# MainBoard_MCU_RF.net
KiCad netlist of a schematic drawn in Altium Designer
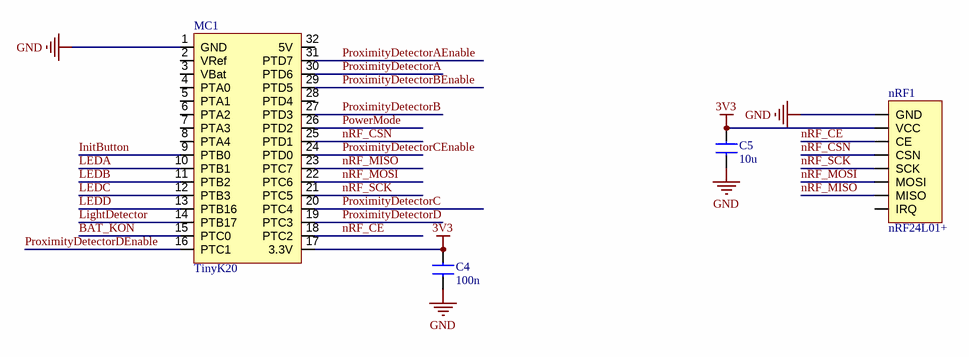
[diagram p0: MainBoard_MCU_RF.SchDoc]

(export (version "E")
  (design (tool "Eeschema 10.0.6"))
  (components
    (comp (ref "C4")
      (value "100n")
      (footprint "0805_C")
      (description "Normaler Kondensator")
      (libsource (lib "MainBoard") (part "C?"))
    )
    (comp (ref "C5")
      (value "10u")
      (footprint "0805_C")
      (description "Normaler Kondensator")
      (libsource (lib "MainBoard") (part "C?"))
    )
    (comp (ref "MC1") (value "TinyK20") (footprint "DIP32") (libsource (lib "MainBoard") (part "TinyK20")))
    (comp (ref "nRF1")
      (value "nRF24L01+")
      (footprint "CON_THT_2x4P_RM2.54_Stiftl")
      (libsource (lib "MainBoard") (part "Bluefruit"))
    )
  )
  (nets
    (net (code "1") (name "/BAT_KON") (class "Default")
      (node (ref "MC1") (pin "15") (pinfunction "PTC0_15") (pintype "passive"))
    )
    (net (code "2") (name "/InitButton") (class "Default")
      (node (ref "MC1") (pin "9") (pinfunction "PTB0_9") (pintype "passive"))
    )
    (net (code "3") (name "/LEDA") (class "Default")
      (node (ref "MC1") (pin "10") (pinfunction "PTB1_10") (pintype "passive"))
    )
    (net (code "4") (name "/LEDB") (class "Default")
      (node (ref "MC1") (pin "11") (pinfunction "PTB2_11") (pintype "passive"))
    )
    (net (code "5") (name "/LEDC") (class "Default")
      (node (ref "MC1") (pin "12") (pinfunction "PTB3_12") (pintype "passive"))
    )
    (net (code "6") (name "/LEDD") (class "Default")
      (node (ref "MC1") (pin "13") (pinfunction "PTB16_13") (pintype "passive"))
    )
    (net (code "7") (name "/LightDetector") (class "Default")
      (node (ref "MC1") (pin "14") (pinfunction "PTB17_14") (pintype "passive"))
    )
    (net (code "8") (name "/PowerMode") (class "Default")
      (node (ref "MC1") (pin "26") (pinfunction "PTD2_26") (pintype "passive"))
    )
    (net (code "9") (name "/ProximityDetectorA") (class "Default")
      (node (ref "MC1") (pin "30") (pinfunction "PTD6_30") (pintype "passive"))
    )
    (net (code "10") (name "/ProximityDetectorAEnable") (class "Default")
      (node (ref "MC1") (pin "31") (pinfunction "PTD7_31") (pintype "passive"))
    )
    (net (code "11") (name "/ProximityDetectorB") (class "Default")
      (node (ref "MC1") (pin "27") (pinfunction "PTD3_27") (pintype "passive"))
    )
    (net (code "12") (name "/ProximityDetectorBEnable") (class "Default")
      (node (ref "MC1") (pin "29") (pinfunction "PTD5_29") (pintype "passive"))
    )
    (net (code "13") (name "/ProximityDetectorC") (class "Default")
      (node (ref "MC1") (pin "20") (pinfunction "PTC4_20") (pintype "passive"))
    )
    (net (code "14") (name "/ProximityDetectorCEnable") (class "Default")
      (node (ref "MC1") (pin "24") (pinfunction "PTD0_24") (pintype "passive"))
    )
    (net (code "15") (name "/ProximityDetectorD") (class "Default")
      (node (ref "MC1") (pin "19") (pinfunction "PTC3_19") (pintype "passive"))
    )
    (net (code "16") (name "/ProximityDetectorDEnable") (class "Default")
      (node (ref "MC1") (pin "16") (pinfunction "PTC1_16") (pintype "passive"))
    )
    (net (code "17") (name "/nRF_CE") (class "Default")
      (node (ref "MC1") (pin "18") (pinfunction "PTC2_18") (pintype "passive"))
      (node (ref "nRF1") (pin "3") (pinfunction "CE_3") (pintype "passive"))
    )
    (net (code "18") (name "/nRF_CSN") (class "Default")
      (node (ref "MC1") (pin "25") (pinfunction "PTD1_25") (pintype "passive"))
      (node (ref "nRF1") (pin "4") (pinfunction "CSN_4") (pintype "passive"))
    )
    (net (code "19") (name "/nRF_MISO") (class "Default")
      (node (ref "MC1") (pin "23") (pinfunction "PTC7_23") (pintype "passive"))
      (node (ref "nRF1") (pin "7") (pinfunction "MISO_7") (pintype "passive"))
    )
    (net (code "20") (name "/nRF_MOSI") (class "Default")
      (node (ref "MC1") (pin "22") (pinfunction "PTC6_22") (pintype "passive"))
      (node (ref "nRF1") (pin "6") (pinfunction "MOSI_6") (pintype "passive"))
    )
    (net (code "21") (name "/nRF_SCK") (class "Default")
      (node (ref "MC1") (pin "21") (pinfunction "PTC5_21") (pintype "passive"))
      (node (ref "nRF1") (pin "5") (pinfunction "SCK_5") (pintype "passive"))
    )
    (net (code "22") (name "3V3") (class "Default")
      (node (ref "C4") (pin "2") (pinfunction "2_2") (pintype "passive"))
      (node (ref "C5") (pin "2") (pinfunction "2_2") (pintype "passive"))
      (node (ref "MC1") (pin "17") (pinfunction "3.3V_17") (pintype "passive"))
      (node (ref "nRF1") (pin "2") (pinfunction "VCC_2") (pintype "passive"))
    )
    (net (code "23") (name "GND") (class "Default")
      (node (ref "C4") (pin "1") (pinfunction "1_1") (pintype "passive"))
      (node (ref "C5") (pin "1") (pinfunction "1_1") (pintype "passive"))
      (node (ref "MC1") (pin "1") (pinfunction "GND_1") (pintype "passive"))
      (node (ref "nRF1") (pin "1") (pinfunction "GND_1") (pintype "passive"))
    )
    (net (code "24") (name "unconnected-(MC1-5V-Pad32)") (class "Default")
      (node (ref "MC1") (pin "32") (pinfunction "5V_32") (pintype "passive"))
    )
    (net (code "25") (name "unconnected-(MC1-PTA0-Pad4)") (class "Default")
      (node (ref "MC1") (pin "4") (pinfunction "PTA0_4") (pintype "passive"))
    )
    (net (code "26") (name "unconnected-(MC1-PTA1-Pad5)") (class "Default")
      (node (ref "MC1") (pin "5") (pinfunction "PTA1_5") (pintype "passive"))
    )
    (net (code "27") (name "unconnected-(MC1-PTA2-Pad6)") (class "Default")
      (node (ref "MC1") (pin "6") (pinfunction "PTA2_6") (pintype "passive"))
    )
    (net (code "28") (name "unconnected-(MC1-PTA3-Pad7)") (class "Default")
      (node (ref "MC1") (pin "7") (pinfunction "PTA3_7") (pintype "passive"))
    )
    (net (code "29") (name "unconnected-(MC1-PTA4-Pad8)") (class "Default")
      (node (ref "MC1") (pin "8") (pinfunction "PTA4_8") (pintype "passive"))
    )
    (net (code "30") (name "unconnected-(MC1-PTD4-Pad28)") (class "Default")
      (node (ref "MC1") (pin "28") (pinfunction "PTD4_28") (pintype "passive"))
    )
    (net (code "31") (name "unconnected-(MC1-VBat-Pad3)") (class "Default")
      (node (ref "MC1") (pin "3") (pinfunction "VBat_3") (pintype "passive"))
    )
    (net (code "32") (name "unconnected-(MC1-VRef-Pad2)") (class "Default")
      (node (ref "MC1") (pin "2") (pinfunction "VRef_2") (pintype "passive"))
    )
    (net (code "33") (name "unconnected-(nRF1-IRQ-Pad8)") (class "Default")
      (node (ref "nRF1") (pin "8") (pinfunction "IRQ_8") (pintype "passive"))
    )
  )
)
